# Sheet_1_2021-08-28_22-45-47.net
KiCad netlist of a schematic drawn in Altium Designer
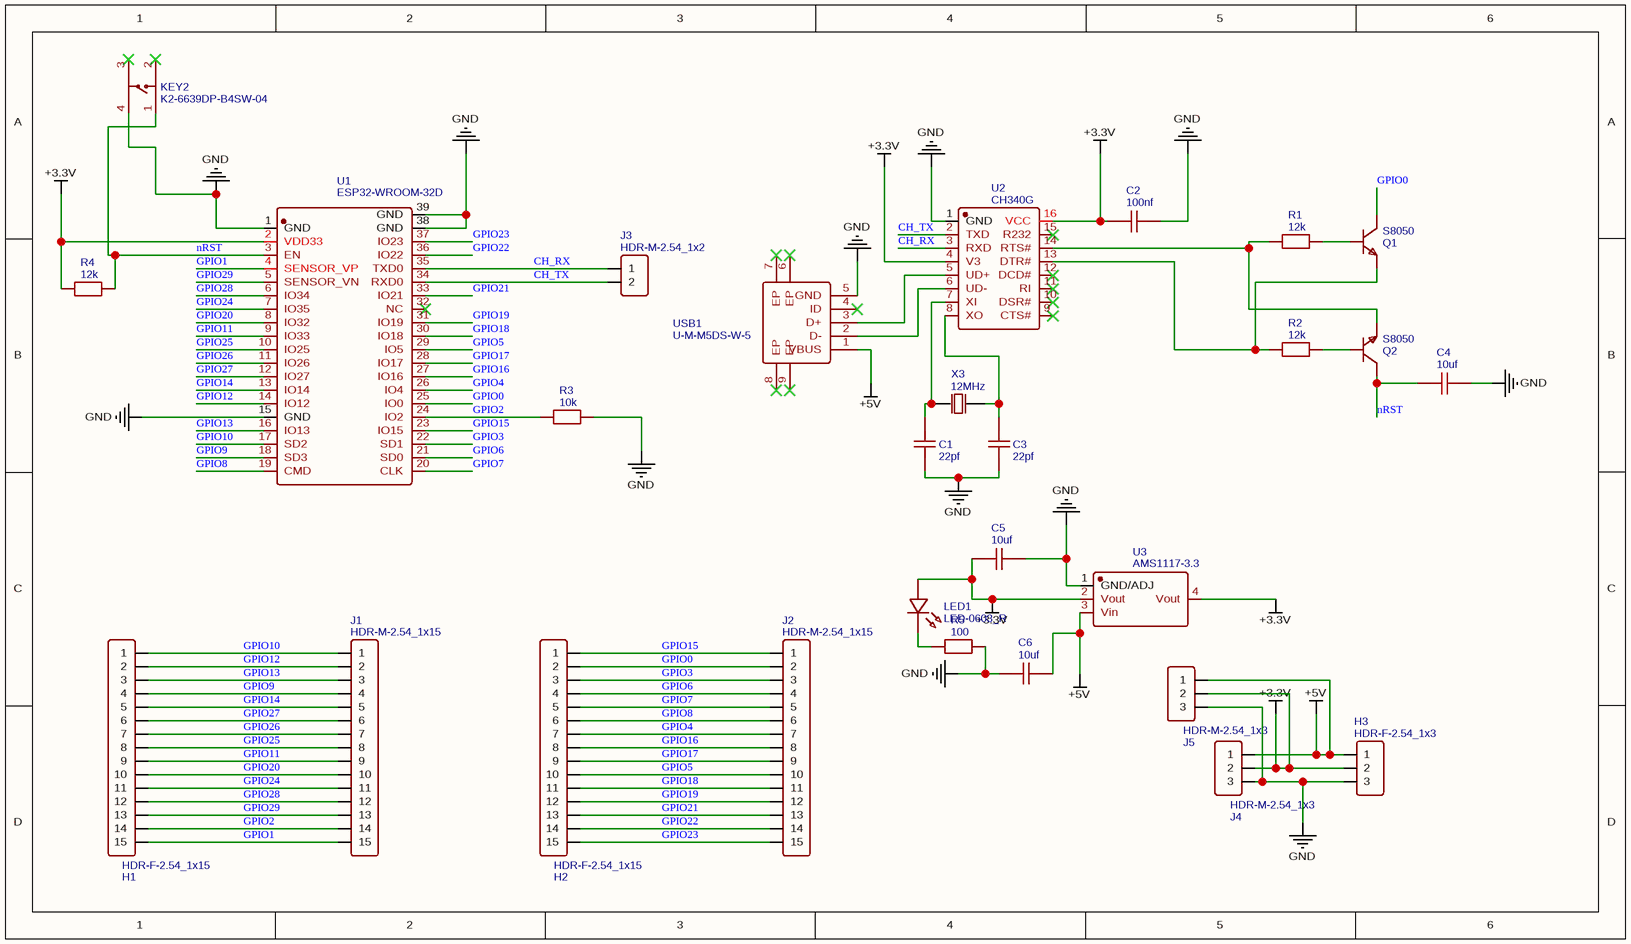
[diagram p0: Sheet_1_2021-08-28_22-45-47.schdoc]

(export (version "E")
  (design (tool "Eeschema 10.0.6"))
  (components
    (comp (ref "C1")
      (value "22pf")
      (fields
        (field (name "BOM_SUPPLIER PART") "C377845")
        (field (name "BOM_MANUFACTURER PART") "CC1H223ZC1FD3F4D1000")
        (field (name "CONTRIBUTOR") "LCSC")
      )
      (libsource (lib "altium-import") (part "root_1_22pf_"))
    )
    (comp (ref "C2")
      (value "100nf")
      (fields
        (field (name "BOM_SUPPLIER PART") "C377845")
        (field (name "BOM_MANUFACTURER PART") "CC1H223ZC1FD3F4D1000")
        (field (name "CONTRIBUTOR") "LCSC")
      )
      (libsource (lib "altium-import") (part "root_0_100nf_"))
    )
    (comp (ref "C3")
      (value "22pf")
      (fields
        (field (name "BOM_SUPPLIER PART") "C377845")
        (field (name "BOM_MANUFACTURER PART") "CC1H223ZC1FD3F4D1000")
        (field (name "CONTRIBUTOR") "LCSC")
      )
      (libsource (lib "altium-import") (part "root_1_22pf_"))
    )
    (comp (ref "C4")
      (value "10uf")
      (fields
        (field (name "BOM_SUPPLIER PART") "C377845")
        (field (name "BOM_MANUFACTURER PART") "CC1H223ZC1FD3F4D1000")
        (field (name "CONTRIBUTOR") "LCSC")
      )
      (libsource (lib "altium-import") (part "root_0_10uf_"))
    )
    (comp (ref "C5")
      (value "10uf")
      (fields
        (field (name "BOM_SUPPLIER PART") "C377845")
        (field (name "BOM_MANUFACTURER PART") "CC1H223ZC1FD3F4D1000")
        (field (name "CONTRIBUTOR") "LCSC")
      )
      (libsource (lib "altium-import") (part "root_0_10uf_"))
    )
    (comp (ref "C6")
      (value "10uf")
      (fields
        (field (name "BOM_SUPPLIER PART") "C377845")
        (field (name "BOM_MANUFACTURER PART") "CC1H223ZC1FD3F4D1000")
        (field (name "CONTRIBUTOR") "LCSC")
      )
      (libsource (lib "altium-import") (part "root_0_10uf_"))
    )
    (comp (ref "H1")
      (value "HDR-F-2.54_1x15")
      (fields (field (name "BOM_SUPPLIER PART") "C124408") (field (name "CONTRIBUTOR") "LCEDA_Lib"))
      (libsource (lib "altium-import") (part "root_2_HDR-F-2.54_1x15_"))
    )
    (comp (ref "H2")
      (value "HDR-F-2.54_1x15")
      (fields (field (name "BOM_SUPPLIER PART") "C124408") (field (name "CONTRIBUTOR") "LCEDA_Lib"))
      (libsource (lib "altium-import") (part "root_2_HDR-F-2.54_1x15_"))
    )
    (comp (ref "H3")
      (value "HDR-F-2.54_1x3")
      (fields (field (name "BOM_SUPPLIER PART") "C146690") (field (name "CONTRIBUTOR") "LCEDA_Lib"))
      (libsource (lib "altium-import") (part "root_0_HDR-F-2.54_1x3_"))
    )
    (comp (ref "J1")
      (value "HDR-M-2.54_1x15")
      (fields (field (name "BOM_SUPPLIER PART") "C124373") (field (name "CONTRIBUTOR") "LCEDA_Lib"))
      (libsource (lib "altium-import") (part "root_0_HDR-M-2.54_1x15_"))
    )
    (comp (ref "J2")
      (value "HDR-M-2.54_1x15")
      (fields (field (name "BOM_SUPPLIER PART") "C124373") (field (name "CONTRIBUTOR") "LCEDA_Lib"))
      (libsource (lib "altium-import") (part "root_0_HDR-M-2.54_1x15_"))
    )
    (comp (ref "J3")
      (value "HDR-M-2.54_1x2")
      (fields (field (name "BOM_SUPPLIER PART") "C124375") (field (name "CONTRIBUTOR") "LCEDA_Lib"))
      (libsource (lib "altium-import") (part "root_0_HDR-M-2.54_1x2_"))
    )
    (comp (ref "J4")
      (value "HDR-M-2.54_1x3")
      (fields (field (name "BOM_SUPPLIER PART") "C180248") (field (name "CONTRIBUTOR") "LCEDA_Lib"))
      (libsource (lib "altium-import") (part "root_2_HDR-M-2.54_1x3_"))
    )
    (comp (ref "J5")
      (value "HDR-M-2.54_1x3")
      (fields (field (name "BOM_SUPPLIER PART") "C180248") (field (name "CONTRIBUTOR") "LCEDA_Lib"))
      (libsource (lib "altium-import") (part "root_2_HDR-M-2.54_1x3_"))
    )
    (comp (ref "KEY2")
      (value "K2-6639DP-B4SW-04")
      (fields (field (name "BOM_SUPPLIER PART") "C83205"))
      (libsource (lib "altium-import") (part "root_1_K2-6639DP-B4SW-04_"))
    )
    (comp (ref "LED1")
      (value "LED-0603_R")
      (fields
        (field (name "BOM_MANUFACTURER PART") "19-217/R6C-AL1M2VY/3T")
        (field (name "BOM_SUPPLIER PART") "C72044")
        (field (name "CONTRIBUTOR") "LCEDA_01")
      )
      (libsource (lib "altium-import") (part "root_3_LED-0603_R_"))
    )
    (comp (ref "Q1")
      (value "S8050")
      (fields (field (name "BOM_SUPPLIER PART") "C916390") (field (name "CONTRIBUTOR") "LCSC"))
      (libsource (lib "altium-import") (part "root_0_S8050_"))
    )
    (comp (ref "Q2")
      (value "S8050")
      (fields (field (name "BOM_SUPPLIER PART") "C916390") (field (name "CONTRIBUTOR") "LCSC"))
      (libsource (lib "") (part "root_0_S8050__1"))
    )
    (comp (ref "R1")
      (value "12k")
      (fields (field (name "CONTRIBUTOR") "LCEDA_Lib"))
      (libsource (lib "altium-import") (part "root_0_12k_"))
    )
    (comp (ref "R2")
      (value "12k")
      (fields (field (name "CONTRIBUTOR") "LCEDA_Lib"))
      (libsource (lib "altium-import") (part "root_0_12k_"))
    )
    (comp (ref "R3")
      (value "10k")
      (fields (field (name "CONTRIBUTOR") "LCEDA_Lib"))
      (libsource (lib "altium-import") (part "root_0_10k_"))
    )
    (comp (ref "R4")
      (value "12k")
      (fields (field (name "CONTRIBUTOR") "LCEDA_Lib"))
      (libsource (lib "altium-import") (part "root_0_12k_"))
    )
    (comp (ref "R5")
      (value "100")
      (fields (field (name "CONTRIBUTOR") "LCEDA_Lib"))
      (libsource (lib "altium-import") (part "root_0_100_"))
    )
    (comp (ref "U1")
      (value "ESP32-WROOM-32D")
      (fields (field (name "BOM_SUPPLIER PART") "C473012") (field (name "CONTRIBUTOR") "LCSC"))
      (libsource (lib "altium-import") (part "root_0_ESP32-WROOM-32D_"))
    )
    (comp (ref "U2")
      (value "CH340G")
      (fields (field (name "BOM_SUPPLIER PART") "C14267"))
      (libsource (lib "altium-import") (part "root_0_CH340G_"))
    )
    (comp (ref "U3")
      (value "AMS1117-3.3")
      (fields (field (name "BOM_SUPPLIER PART") "C6186"))
      (libsource (lib "altium-import") (part "root_0_AMS1117-3.3_"))
    )
    (comp (ref "USB1")
      (value "U-M-M5DS-W-5")
      (fields (field (name "BOM_SUPPLIER PART") "C145777") (field (name "CONTRIBUTOR") "LCSC"))
      (libsource (lib "altium-import") (part "root_2_U-M-M5DS-W-5_"))
    )
    (comp (ref "X3")
      (value "12MHz")
      (fields
        (field (name "BOM_MANUFACTURER PART") "X49SD12MSD2SC")
        (field (name "BOM_SUPPLIER PART") "C16369")
      )
      (libsource (lib "altium-import") (part "root_2_12MHz_"))
    )
  )
  (nets
    (net (code "1") (name "+3.3V") (class "Default")
      (node (ref "C2") (pin "1") (pinfunction "1_1") (pintype "passive"))
      (node (ref "C5") (pin "1") (pinfunction "1_1") (pintype "passive"))
      (node (ref "H3") (pin "2") (pinfunction "2_2") (pintype "passive"))
      (node (ref "J4") (pin "2") (pinfunction "2_2") (pintype "passive"))
      (node (ref "J5") (pin "2") (pinfunction "2_2") (pintype "passive"))
      (node (ref "LED1") (pin "1") (pinfunction "1_1") (pintype "passive"))
      (node (ref "R4") (pin "1") (pinfunction "1_1") (pintype "passive"))
      (node (ref "U1") (pin "2") (pinfunction "VDD33_2") (pintype "passive"))
      (node (ref "U2") (pin "16") (pinfunction "VCC_16") (pintype "passive"))
      (node (ref "U2") (pin "4") (pinfunction "V3_4") (pintype "passive"))
      (node (ref "U3") (pin "2") (pinfunction "Vout_2") (pintype "passive"))
      (node (ref "U3") (pin "4") (pinfunction "Vout_4") (pintype "passive"))
    )
    (net (code "2") (name "+5V") (class "Default")
      (node (ref "C6") (pin "2") (pinfunction "2_2") (pintype "passive"))
      (node (ref "H3") (pin "1") (pinfunction "1_1") (pintype "passive"))
      (node (ref "J4") (pin "1") (pinfunction "1_1") (pintype "passive"))
      (node (ref "J5") (pin "1") (pinfunction "1_1") (pintype "passive"))
      (node (ref "U3") (pin "3") (pinfunction "Vin_3") (pintype "passive"))
      (node (ref "USB1") (pin "1") (pinfunction "VBUS_1") (pintype "passive"))
    )
    (net (code "3") (name "/CH_RX") (class "Default")
      (node (ref "J3") (pin "1") (pinfunction "1_1") (pintype "passive"))
      (node (ref "U1") (pin "35") (pinfunction "TXD0_35") (pintype "passive"))
      (node (ref "U2") (pin "3") (pinfunction "RXD_3") (pintype "passive"))
    )
    (net (code "4") (name "/CH_TX") (class "Default")
      (node (ref "J3") (pin "2") (pinfunction "2_2") (pintype "passive"))
      (node (ref "U1") (pin "34") (pinfunction "RXD0_34") (pintype "passive"))
      (node (ref "U2") (pin "2") (pinfunction "TXD_2") (pintype "passive"))
    )
    (net (code "5") (name "/GPIO0") (class "Default")
      (node (ref "H2") (pin "2") (pinfunction "2_2") (pintype "passive"))
      (node (ref "J2") (pin "2") (pinfunction "2_2") (pintype "passive"))
      (node (ref "Q1") (pin "3") (pinfunction "C_3") (pintype "passive"))
      (node (ref "U1") (pin "25") (pinfunction "IO0_25") (pintype "passive"))
    )
    (net (code "6") (name "/GPIO1") (class "Default")
      (node (ref "H1") (pin "15") (pinfunction "15_15") (pintype "passive"))
      (node (ref "J1") (pin "15") (pinfunction "15_15") (pintype "passive"))
      (node (ref "U1") (pin "4") (pinfunction "SENSOR_VP_4") (pintype "passive"))
    )
    (net (code "7") (name "/GPIO2") (class "Default")
      (node (ref "H1") (pin "14") (pinfunction "14_14") (pintype "passive"))
      (node (ref "J1") (pin "14") (pinfunction "14_14") (pintype "passive"))
      (node (ref "R3") (pin "1") (pinfunction "1_1") (pintype "passive"))
      (node (ref "U1") (pin "24") (pinfunction "IO2_24") (pintype "passive"))
    )
    (net (code "8") (name "/GPIO3") (class "Default")
      (node (ref "H2") (pin "3") (pinfunction "3_3") (pintype "passive"))
      (node (ref "J2") (pin "3") (pinfunction "3_3") (pintype "passive"))
      (node (ref "U1") (pin "22") (pinfunction "SD1_22") (pintype "passive"))
    )
    (net (code "9") (name "/GPIO4") (class "Default")
      (node (ref "H2") (pin "7") (pinfunction "7_7") (pintype "passive"))
      (node (ref "J2") (pin "7") (pinfunction "7_7") (pintype "passive"))
      (node (ref "U1") (pin "26") (pinfunction "IO4_26") (pintype "passive"))
    )
    (net (code "10") (name "/GPIO5") (class "Default")
      (node (ref "H2") (pin "10") (pinfunction "10_10") (pintype "passive"))
      (node (ref "J2") (pin "10") (pinfunction "10_10") (pintype "passive"))
      (node (ref "U1") (pin "29") (pinfunction "IO5_29") (pintype "passive"))
    )
    (net (code "11") (name "/GPIO6") (class "Default")
      (node (ref "H2") (pin "4") (pinfunction "4_4") (pintype "passive"))
      (node (ref "J2") (pin "4") (pinfunction "4_4") (pintype "passive"))
      (node (ref "U1") (pin "21") (pinfunction "SD0_21") (pintype "passive"))
    )
    (net (code "12") (name "/GPIO7") (class "Default")
      (node (ref "H2") (pin "5") (pinfunction "5_5") (pintype "passive"))
      (node (ref "J2") (pin "5") (pinfunction "5_5") (pintype "passive"))
      (node (ref "U1") (pin "20") (pinfunction "CLK_20") (pintype "passive"))
    )
    (net (code "13") (name "/GPIO8") (class "Default")
      (node (ref "H2") (pin "6") (pinfunction "6_6") (pintype "passive"))
      (node (ref "J2") (pin "6") (pinfunction "6_6") (pintype "passive"))
      (node (ref "U1") (pin "19") (pinfunction "CMD_19") (pintype "passive"))
    )
    (net (code "14") (name "/GPIO9") (class "Default")
      (node (ref "H1") (pin "4") (pinfunction "4_4") (pintype "passive"))
      (node (ref "J1") (pin "4") (pinfunction "4_4") (pintype "passive"))
      (node (ref "U1") (pin "18") (pinfunction "SD3_18") (pintype "passive"))
    )
    (net (code "15") (name "/GPIO10") (class "Default")
      (node (ref "H1") (pin "1") (pinfunction "1_1") (pintype "passive"))
      (node (ref "J1") (pin "1") (pinfunction "1_1") (pintype "passive"))
      (node (ref "U1") (pin "17") (pinfunction "SD2_17") (pintype "passive"))
    )
    (net (code "16") (name "/GPIO11") (class "Default")
      (node (ref "H1") (pin "9") (pinfunction "9_9") (pintype "passive"))
      (node (ref "J1") (pin "9") (pinfunction "9_9") (pintype "passive"))
      (node (ref "U1") (pin "9") (pinfunction "IO33_9") (pintype "passive"))
    )
    (net (code "17") (name "/GPIO12") (class "Default")
      (node (ref "H1") (pin "2") (pinfunction "2_2") (pintype "passive"))
      (node (ref "J1") (pin "2") (pinfunction "2_2") (pintype "passive"))
      (node (ref "U1") (pin "14") (pinfunction "IO12_14") (pintype "passive"))
    )
    (net (code "18") (name "/GPIO13") (class "Default")
      (node (ref "H1") (pin "3") (pinfunction "3_3") (pintype "passive"))
      (node (ref "J1") (pin "3") (pinfunction "3_3") (pintype "passive"))
      (node (ref "U1") (pin "16") (pinfunction "IO13_16") (pintype "passive"))
    )
    (net (code "19") (name "/GPIO14") (class "Default")
      (node (ref "H1") (pin "5") (pinfunction "5_5") (pintype "passive"))
      (node (ref "J1") (pin "5") (pinfunction "5_5") (pintype "passive"))
      (node (ref "U1") (pin "13") (pinfunction "IO14_13") (pintype "passive"))
    )
    (net (code "20") (name "/GPIO15") (class "Default")
      (node (ref "H2") (pin "1") (pinfunction "1_1") (pintype "passive"))
      (node (ref "J2") (pin "1") (pinfunction "1_1") (pintype "passive"))
      (node (ref "U1") (pin "23") (pinfunction "IO15_23") (pintype "passive"))
    )
    (net (code "21") (name "/GPIO16") (class "Default")
      (node (ref "H2") (pin "8") (pinfunction "8_8") (pintype "passive"))
      (node (ref "J2") (pin "8") (pinfunction "8_8") (pintype "passive"))
      (node (ref "U1") (pin "27") (pinfunction "IO16_27") (pintype "passive"))
    )
    (net (code "22") (name "/GPIO17") (class "Default")
      (node (ref "H2") (pin "9") (pinfunction "9_9") (pintype "passive"))
      (node (ref "J2") (pin "9") (pinfunction "9_9") (pintype "passive"))
      (node (ref "U1") (pin "28") (pinfunction "IO17_28") (pintype "passive"))
    )
    (net (code "23") (name "/GPIO18") (class "Default")
      (node (ref "H2") (pin "11") (pinfunction "11_11") (pintype "passive"))
      (node (ref "J2") (pin "11") (pinfunction "11_11") (pintype "passive"))
      (node (ref "U1") (pin "30") (pinfunction "IO18_30") (pintype "passive"))
    )
    (net (code "24") (name "/GPIO19") (class "Default")
      (node (ref "H2") (pin "12") (pinfunction "12_12") (pintype "passive"))
      (node (ref "J2") (pin "12") (pinfunction "12_12") (pintype "passive"))
      (node (ref "U1") (pin "31") (pinfunction "IO19_31") (pintype "passive"))
    )
    (net (code "25") (name "/GPIO20") (class "Default")
      (node (ref "H1") (pin "10") (pinfunction "10_10") (pintype "passive"))
      (node (ref "J1") (pin "10") (pinfunction "10_10") (pintype "passive"))
      (node (ref "U1") (pin "8") (pinfunction "IO32_8") (pintype "passive"))
    )
    (net (code "26") (name "/GPIO21") (class "Default")
      (node (ref "H2") (pin "13") (pinfunction "13_13") (pintype "passive"))
      (node (ref "J2") (pin "13") (pinfunction "13_13") (pintype "passive"))
      (node (ref "U1") (pin "33") (pinfunction "IO21_33") (pintype "passive"))
    )
    (net (code "27") (name "/GPIO22") (class "Default")
      (node (ref "H2") (pin "14") (pinfunction "14_14") (pintype "passive"))
      (node (ref "J2") (pin "14") (pinfunction "14_14") (pintype "passive"))
      (node (ref "U1") (pin "36") (pinfunction "IO22_36") (pintype "passive"))
    )
    (net (code "28") (name "/GPIO23") (class "Default")
      (node (ref "H2") (pin "15") (pinfunction "15_15") (pintype "passive"))
      (node (ref "J2") (pin "15") (pinfunction "15_15") (pintype "passive"))
      (node (ref "U1") (pin "37") (pinfunction "IO23_37") (pintype "passive"))
    )
    (net (code "29") (name "/GPIO24") (class "Default")
      (node (ref "H1") (pin "11") (pinfunction "11_11") (pintype "passive"))
      (node (ref "J1") (pin "11") (pinfunction "11_11") (pintype "passive"))
      (node (ref "U1") (pin "7") (pinfunction "IO35_7") (pintype "passive"))
    )
    (net (code "30") (name "/GPIO25") (class "Default")
      (node (ref "H1") (pin "8") (pinfunction "8_8") (pintype "passive"))
      (node (ref "J1") (pin "8") (pinfunction "8_8") (pintype "passive"))
      (node (ref "U1") (pin "10") (pinfunction "IO25_10") (pintype "passive"))
    )
    (net (code "31") (name "/GPIO26") (class "Default")
      (node (ref "H1") (pin "7") (pinfunction "7_7") (pintype "passive"))
      (node (ref "J1") (pin "7") (pinfunction "7_7") (pintype "passive"))
      (node (ref "U1") (pin "11") (pinfunction "IO26_11") (pintype "passive"))
    )
    (net (code "32") (name "/GPIO27") (class "Default")
      (node (ref "H1") (pin "6") (pinfunction "6_6") (pintype "passive"))
      (node (ref "J1") (pin "6") (pinfunction "6_6") (pintype "passive"))
      (node (ref "U1") (pin "12") (pinfunction "IO27_12") (pintype "passive"))
    )
    (net (code "33") (name "/GPIO28") (class "Default")
      (node (ref "H1") (pin "12") (pinfunction "12_12") (pintype "passive"))
      (node (ref "J1") (pin "12") (pinfunction "12_12") (pintype "passive"))
      (node (ref "U1") (pin "6") (pinfunction "IO34_6") (pintype "passive"))
    )
    (net (code "34") (name "/GPIO29") (class "Default")
      (node (ref "H1") (pin "13") (pinfunction "13_13") (pintype "passive"))
      (node (ref "J1") (pin "13") (pinfunction "13_13") (pintype "passive"))
      (node (ref "U1") (pin "5") (pinfunction "SENSOR_VN_5") (pintype "passive"))
    )
    (net (code "35") (name "/nRST") (class "Default")
      (node (ref "C4") (pin "1") (pinfunction "1_1") (pintype "passive"))
      (node (ref "KEY2") (pin "1") (pinfunction "1_1") (pintype "passive"))
      (node (ref "Q2") (pin "3") (pinfunction "C_3") (pintype "passive"))
      (node (ref "R4") (pin "2") (pinfunction "2_2") (pintype "passive"))
      (node (ref "U1") (pin "3") (pinfunction "EN_3") (pintype "passive"))
    )
    (net (code "36") (name "GND") (class "Default")
      (node (ref "C1") (pin "1") (pinfunction "1_1") (pintype "passive"))
      (node (ref "C2") (pin "2") (pinfunction "2_2") (pintype "passive"))
      (node (ref "C3") (pin "1") (pinfunction "1_1") (pintype "passive"))
      (node (ref "C4") (pin "2") (pinfunction "2_2") (pintype "passive"))
      (node (ref "C5") (pin "2") (pinfunction "2_2") (pintype "passive"))
      (node (ref "C6") (pin "1") (pinfunction "1_1") (pintype "passive"))
      (node (ref "H3") (pin "3") (pinfunction "3_3") (pintype "passive"))
      (node (ref "J4") (pin "3") (pinfunction "3_3") (pintype "passive"))
      (node (ref "J5") (pin "3") (pinfunction "3_3") (pintype "passive"))
      (node (ref "KEY2") (pin "4") (pinfunction "4_4") (pintype "passive"))
      (node (ref "R3") (pin "2") (pinfunction "2_2") (pintype "passive"))
      (node (ref "R5") (pin "2") (pinfunction "2_2") (pintype "passive"))
      (node (ref "U1") (pin "1") (pinfunction "GND_1") (pintype "passive"))
      (node (ref "U1") (pin "15") (pinfunction "GND_15") (pintype "passive"))
      (node (ref "U1") (pin "38") (pinfunction "GND_38") (pintype "passive"))
      (node (ref "U1") (pin "39") (pinfunction "GND_39") (pintype "passive"))
      (node (ref "U2") (pin "1") (pinfunction "GND_1") (pintype "passive"))
      (node (ref "U3") (pin "1") (pinfunction "GND/ADJ_1") (pintype "passive"))
      (node (ref "USB1") (pin "5") (pinfunction "GND_5") (pintype "passive"))
    )
    (net (code "37") (name "Net-(LED1-Pad2)") (class "Default")
      (node (ref "LED1") (pin "2") (pinfunction "2_2") (pintype "passive"))
      (node (ref "R5") (pin "1") (pinfunction "1_1") (pintype "passive"))
    )
    (net (code "38") (name "Net-(Q1-B)") (class "Default")
      (node (ref "Q1") (pin "1") (pinfunction "B_1") (pintype "passive"))
      (node (ref "R1") (pin "2") (pinfunction "2_2") (pintype "passive"))
    )
    (net (code "39") (name "Net-(Q1-E)") (class "Default")
      (node (ref "Q1") (pin "2") (pinfunction "E_2") (pintype "passive"))
      (node (ref "R2") (pin "1") (pinfunction "1_1") (pintype "passive"))
      (node (ref "U2") (pin "13") (pinfunction "DTR#_13") (pintype "passive"))
    )
    (net (code "40") (name "Net-(Q2-B)") (class "Default")
      (node (ref "Q2") (pin "1") (pinfunction "B_1") (pintype "passive"))
      (node (ref "R2") (pin "2") (pinfunction "2_2") (pintype "passive"))
    )
    (net (code "41") (name "Net-(Q2-E)") (class "Default")
      (node (ref "Q2") (pin "2") (pinfunction "E_2") (pintype "passive"))
      (node (ref "R1") (pin "1") (pinfunction "1_1") (pintype "passive"))
      (node (ref "U2") (pin "14") (pinfunction "RTS#_14") (pintype "passive"))
    )
    (net (code "42") (name "Net-(U2-UD+)") (class "Default")
      (node (ref "U2") (pin "5") (pinfunction "UD+_5") (pintype "passive"))
      (node (ref "USB1") (pin "3") (pinfunction "D+_3") (pintype "passive"))
    )
    (net (code "43") (name "Net-(U2-UD-)") (class "Default")
      (node (ref "U2") (pin "6") (pinfunction "UD-_6") (pintype "passive"))
      (node (ref "USB1") (pin "2") (pinfunction "D-_2") (pintype "passive"))
    )
    (net (code "44") (name "Net-(U2-XI)") (class "Default")
      (node (ref "C1") (pin "2") (pinfunction "2_2") (pintype "passive"))
      (node (ref "U2") (pin "7") (pinfunction "XI_7") (pintype "passive"))
      (node (ref "X3") (pin "1") (pinfunction "OSC1_1") (pintype "passive"))
    )
    (net (code "45") (name "Net-(U2-XO)") (class "Default")
      (node (ref "C3") (pin "2") (pinfunction "2_2") (pintype "passive"))
      (node (ref "U2") (pin "8") (pinfunction "XO_8") (pintype "passive"))
      (node (ref "X3") (pin "2") (pinfunction "OSC2_2") (pintype "passive"))
    )
    (net (code "46") (name "unconnected-(KEY2-Pad2)") (class "Default")
      (node (ref "KEY2") (pin "2") (pinfunction "2_2") (pintype "passive+no_connect"))
    )
    (net (code "47") (name "unconnected-(KEY2-Pad3)") (class "Default")
      (node (ref "KEY2") (pin "3") (pinfunction "3_3") (pintype "passive+no_connect"))
    )
    (net (code "48") (name "unconnected-(U1-NC-Pad32)") (class "Default")
      (node (ref "U1") (pin "32") (pinfunction "NC_32") (pintype "passive+no_connect"))
    )
    (net (code "49") (name "unconnected-(U2-CTS#-Pad9)") (class "Default")
      (node (ref "U2") (pin "9") (pinfunction "CTS#_9") (pintype "passive+no_connect"))
    )
    (net (code "50") (name "unconnected-(U2-DCD#-Pad12)") (class "Default")
      (node (ref "U2") (pin "12") (pinfunction "DCD#_12") (pintype "passive+no_connect"))
    )
    (net (code "51") (name "unconnected-(U2-DSR#-Pad10)") (class "Default")
      (node (ref "U2") (pin "10") (pinfunction "DSR#_10") (pintype "passive+no_connect"))
    )
    (net (code "52") (name "unconnected-(U2-R232-Pad15)") (class "Default")
      (node (ref "U2") (pin "15") (pinfunction "R232_15") (pintype "passive+no_connect"))
    )
    (net (code "53") (name "unconnected-(U2-RI-Pad11)") (class "Default")
      (node (ref "U2") (pin "11") (pinfunction "RI_11") (pintype "passive+no_connect"))
    )
    (net (code "54") (name "unconnected-(USB1-EP-Pad6)") (class "Default")
      (node (ref "USB1") (pin "6") (pinfunction "EP_6") (pintype "passive+no_connect"))
    )
    (net (code "55") (name "unconnected-(USB1-EP-Pad7)") (class "Default")
      (node (ref "USB1") (pin "7") (pinfunction "EP_7") (pintype "passive+no_connect"))
    )
    (net (code "56") (name "unconnected-(USB1-EP-Pad8)") (class "Default")
      (node (ref "USB1") (pin "8") (pinfunction "EP_8") (pintype "passive+no_connect"))
    )
    (net (code "57") (name "unconnected-(USB1-EP-Pad9)") (class "Default")
      (node (ref "USB1") (pin "9") (pinfunction "EP_9") (pintype "passive+no_connect"))
    )
    (net (code "58") (name "unconnected-(USB1-ID-Pad4)") (class "Default")
      (node (ref "USB1") (pin "4") (pinfunction "ID_4") (pintype "passive+no_connect"))
    )
  )
)
